# DSDPLC_IO.net
KiCad netlist of a schematic drawn in Altium Designer
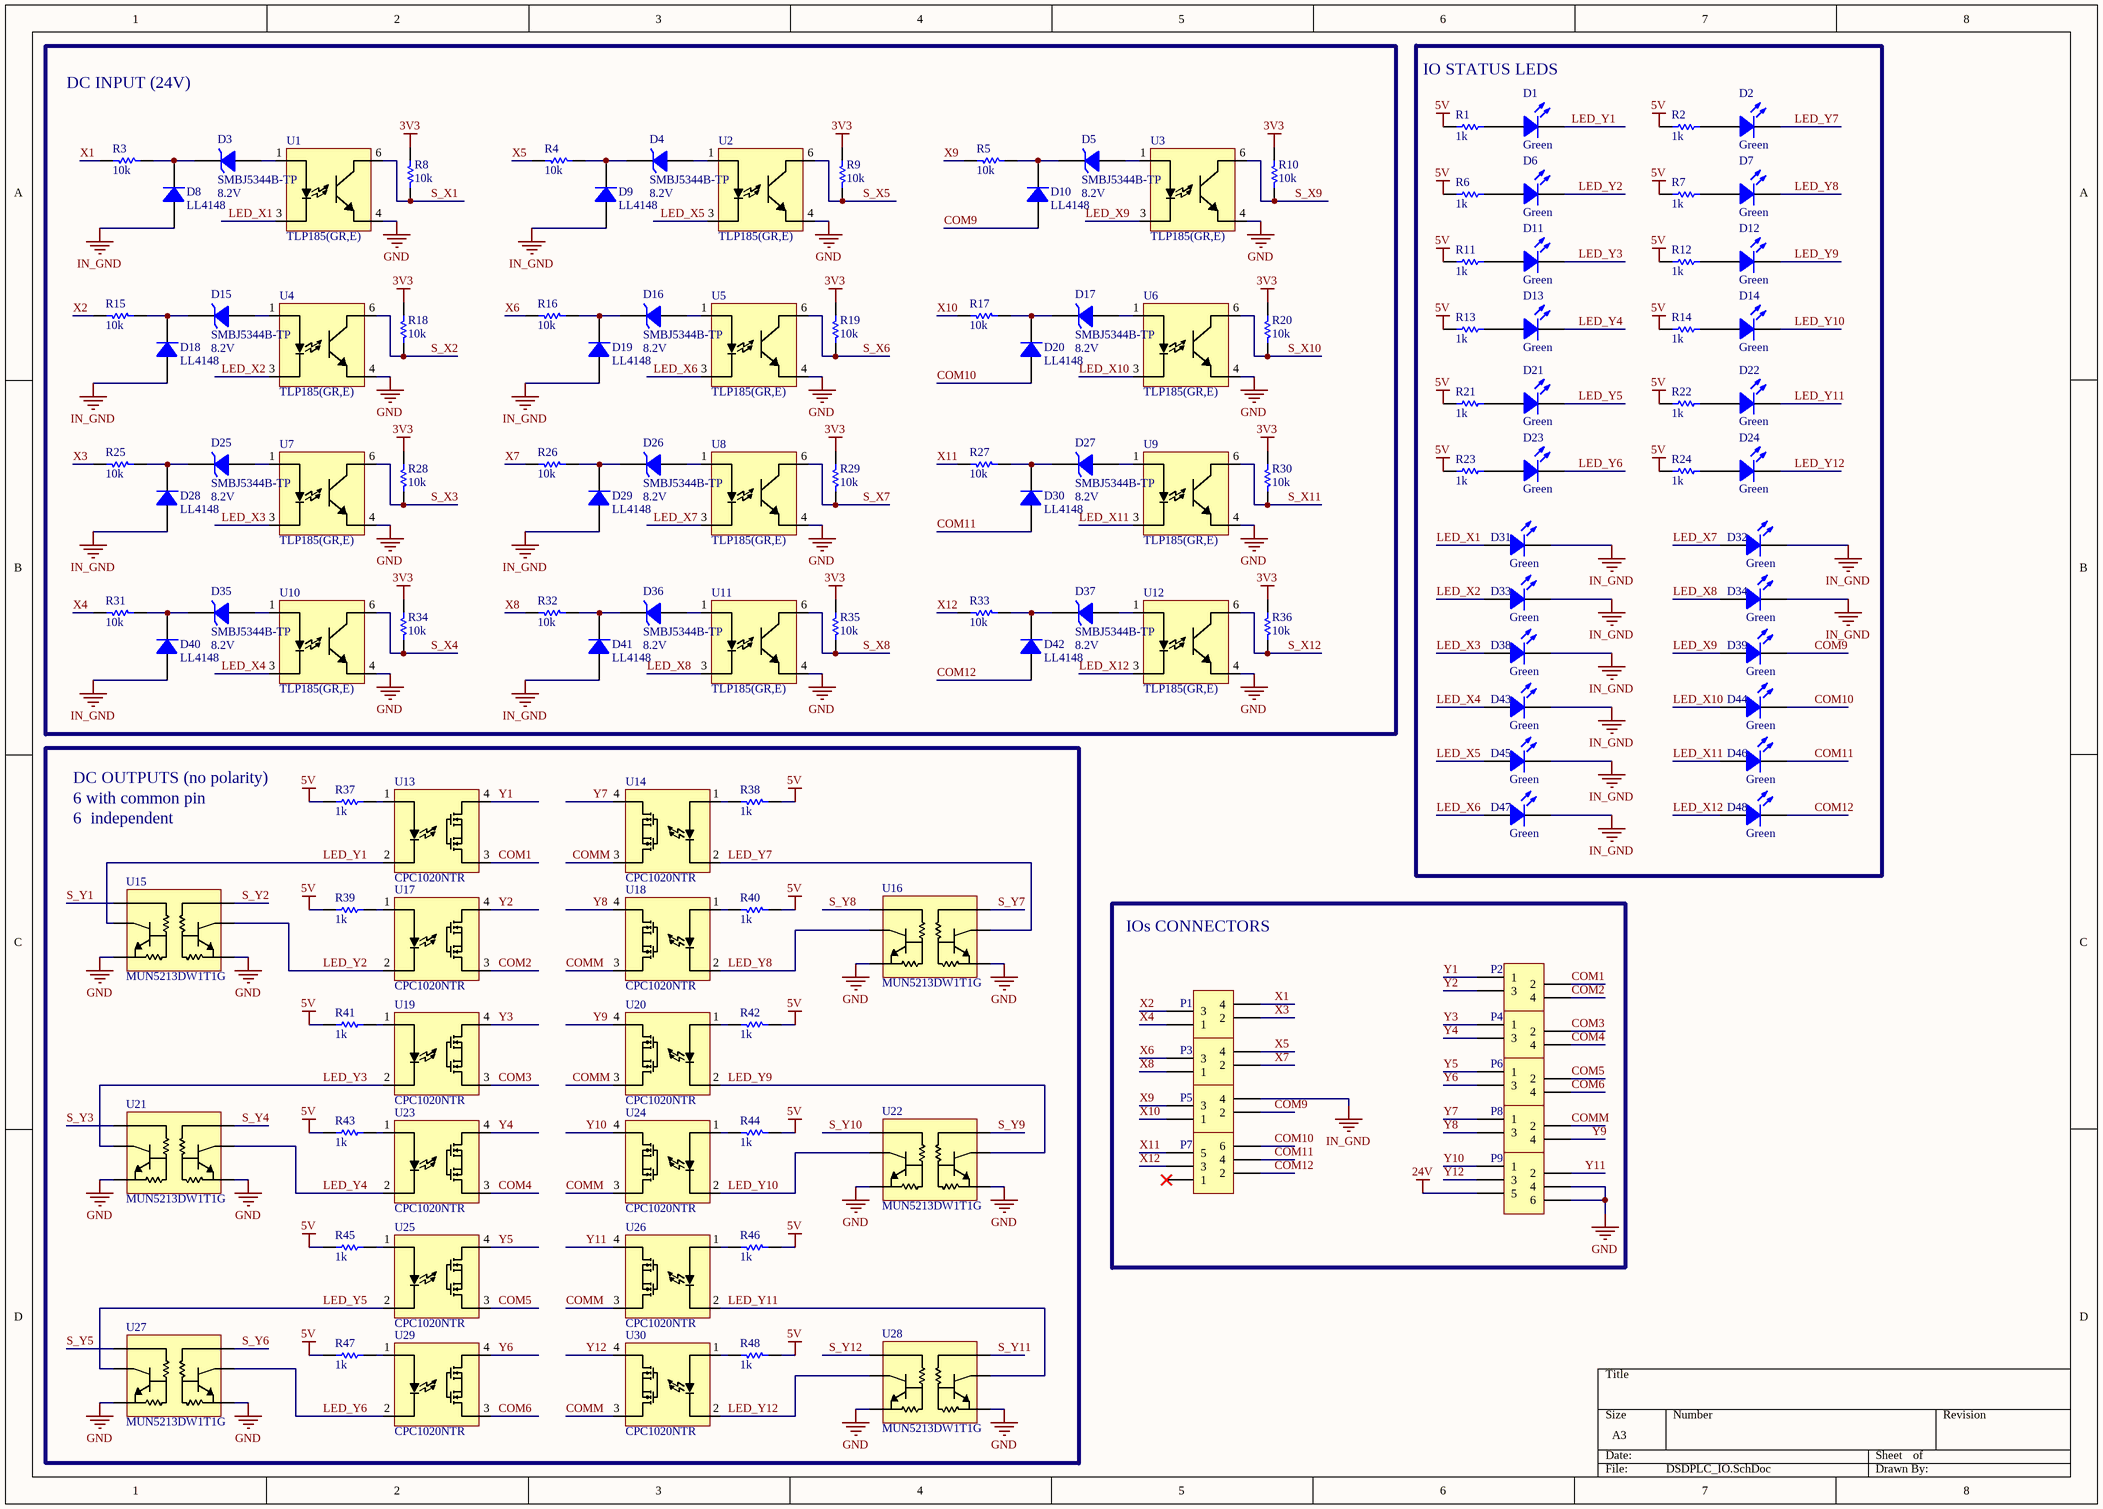
[diagram p0: DSDPLC_IO.SchDoc]

(export (version "E")
  (design (tool "Eeschema 10.0.6"))
  (components
    (comp (ref "D1")
      (value "Green")
      (footprint "R0603_N")
      (fields (field (name "COLOR") "Green"))
      (libsource (lib "General") (part "LED_SMD"))
    )
    (comp (ref "D2")
      (value "Green")
      (footprint "R0603_N")
      (fields (field (name "COLOR") "Green"))
      (libsource (lib "General") (part "LED_SMD"))
    )
    (comp (ref "D3")
      (value "SMBJ5344B-TP")
      (footprint "SMB_N")
      (description "DIODE ZENER 8.2V 5W DO214AA")
      (fields
        (field (name "MANUFACTURER") "Micro Commercial Co")
        (field (name "VOLTAGE - ZENER (NOM) (VZ)") "8.2V")
        (field (name "TOLERANCE") "±5%")
      )
      (libsource (lib "General") (part "SMBJ5344B-TP"))
    )
    (comp (ref "D4")
      (value "SMBJ5344B-TP")
      (footprint "SMB_N")
      (description "DIODE ZENER 8.2V 5W DO214AA")
      (fields
        (field (name "MANUFACTURER") "Micro Commercial Co")
        (field (name "VOLTAGE - ZENER (NOM) (VZ)") "8.2V")
        (field (name "TOLERANCE") "±5%")
      )
      (libsource (lib "General") (part "SMBJ5344B-TP"))
    )
    (comp (ref "D5")
      (value "SMBJ5344B-TP")
      (footprint "SMB_N")
      (description "DIODE ZENER 8.2V 5W DO214AA")
      (fields
        (field (name "MANUFACTURER") "Micro Commercial Co")
        (field (name "VOLTAGE - ZENER (NOM) (VZ)") "8.2V")
        (field (name "TOLERANCE") "±5%")
      )
      (libsource (lib "General") (part "SMBJ5344B-TP"))
    )
    (comp (ref "D6")
      (value "Green")
      (footprint "R0603_N")
      (fields (field (name "COLOR") "Green"))
      (libsource (lib "General") (part "LED_SMD"))
    )
    (comp (ref "D7")
      (value "Green")
      (footprint "R0603_N")
      (fields (field (name "COLOR") "Green"))
      (libsource (lib "General") (part "LED_SMD"))
    )
    (comp (ref "D8")
      (value "LL4148")
      (footprint "SOD-80_N")
      (description "DIODE SMALL SIG 100V 0.2A SOD80")
      (fields (field (name "MANUFACTURER") "Fairchild Semiconductor"))
      (libsource (lib "General") (part "LL4148"))
    )
    (comp (ref "D9")
      (value "LL4148")
      (footprint "SOD-80_N")
      (description "DIODE SMALL SIG 100V 0.2A SOD80")
      (fields (field (name "MANUFACTURER") "Fairchild Semiconductor"))
      (libsource (lib "General") (part "LL4148"))
    )
    (comp (ref "D10")
      (value "LL4148")
      (footprint "SOD-80_N")
      (description "DIODE SMALL SIG 100V 0.2A SOD80")
      (fields (field (name "MANUFACTURER") "Fairchild Semiconductor"))
      (libsource (lib "General") (part "LL4148"))
    )
    (comp (ref "D11")
      (value "Green")
      (footprint "R0603_N")
      (fields (field (name "COLOR") "Green"))
      (libsource (lib "General") (part "LED_SMD"))
    )
    (comp (ref "D12")
      (value "Green")
      (footprint "R0603_N")
      (fields (field (name "COLOR") "Green"))
      (libsource (lib "General") (part "LED_SMD"))
    )
    (comp (ref "D13")
      (value "Green")
      (footprint "R0603_N")
      (fields (field (name "COLOR") "Green"))
      (libsource (lib "General") (part "LED_SMD"))
    )
    (comp (ref "D14")
      (value "Green")
      (footprint "R0603_N")
      (fields (field (name "COLOR") "Green"))
      (libsource (lib "General") (part "LED_SMD"))
    )
    (comp (ref "D15")
      (value "SMBJ5344B-TP")
      (footprint "SMB_N")
      (description "DIODE ZENER 8.2V 5W DO214AA")
      (fields
        (field (name "MANUFACTURER") "Micro Commercial Co")
        (field (name "VOLTAGE - ZENER (NOM) (VZ)") "8.2V")
        (field (name "TOLERANCE") "±5%")
      )
      (libsource (lib "General") (part "SMBJ5344B-TP"))
    )
    (comp (ref "D16")
      (value "SMBJ5344B-TP")
      (footprint "SMB_N")
      (description "DIODE ZENER 8.2V 5W DO214AA")
      (fields
        (field (name "MANUFACTURER") "Micro Commercial Co")
        (field (name "VOLTAGE - ZENER (NOM) (VZ)") "8.2V")
        (field (name "TOLERANCE") "±5%")
      )
      (libsource (lib "General") (part "SMBJ5344B-TP"))
    )
    (comp (ref "D17")
      (value "SMBJ5344B-TP")
      (footprint "SMB_N")
      (description "DIODE ZENER 8.2V 5W DO214AA")
      (fields
        (field (name "MANUFACTURER") "Micro Commercial Co")
        (field (name "VOLTAGE - ZENER (NOM) (VZ)") "8.2V")
        (field (name "TOLERANCE") "±5%")
      )
      (libsource (lib "General") (part "SMBJ5344B-TP"))
    )
    (comp (ref "D18")
      (value "LL4148")
      (footprint "SOD-80_N")
      (description "DIODE SMALL SIG 100V 0.2A SOD80")
      (fields (field (name "MANUFACTURER") "Fairchild Semiconductor"))
      (libsource (lib "General") (part "LL4148"))
    )
    (comp (ref "D19")
      (value "LL4148")
      (footprint "SOD-80_N")
      (description "DIODE SMALL SIG 100V 0.2A SOD80")
      (fields (field (name "MANUFACTURER") "Fairchild Semiconductor"))
      (libsource (lib "General") (part "LL4148"))
    )
    (comp (ref "D20")
      (value "LL4148")
      (footprint "SOD-80_N")
      (description "DIODE SMALL SIG 100V 0.2A SOD80")
      (fields (field (name "MANUFACTURER") "Fairchild Semiconductor"))
      (libsource (lib "General") (part "LL4148"))
    )
    (comp (ref "D21")
      (value "Green")
      (footprint "R0603_N")
      (fields (field (name "COLOR") "Green"))
      (libsource (lib "General") (part "LED_SMD"))
    )
    (comp (ref "D22")
      (value "Green")
      (footprint "R0603_N")
      (fields (field (name "COLOR") "Green"))
      (libsource (lib "General") (part "LED_SMD"))
    )
    (comp (ref "D23")
      (value "Green")
      (footprint "R0603_N")
      (fields (field (name "COLOR") "Green"))
      (libsource (lib "General") (part "LED_SMD"))
    )
    (comp (ref "D24")
      (value "Green")
      (footprint "R0603_N")
      (fields (field (name "COLOR") "Green"))
      (libsource (lib "General") (part "LED_SMD"))
    )
    (comp (ref "D25")
      (value "SMBJ5344B-TP")
      (footprint "SMB_N")
      (description "DIODE ZENER 8.2V 5W DO214AA")
      (fields
        (field (name "MANUFACTURER") "Micro Commercial Co")
        (field (name "VOLTAGE - ZENER (NOM) (VZ)") "8.2V")
        (field (name "TOLERANCE") "±5%")
      )
      (libsource (lib "General") (part "SMBJ5344B-TP"))
    )
    (comp (ref "D26")
      (value "SMBJ5344B-TP")
      (footprint "SMB_N")
      (description "DIODE ZENER 8.2V 5W DO214AA")
      (fields
        (field (name "MANUFACTURER") "Micro Commercial Co")
        (field (name "VOLTAGE - ZENER (NOM) (VZ)") "8.2V")
        (field (name "TOLERANCE") "±5%")
      )
      (libsource (lib "General") (part "SMBJ5344B-TP"))
    )
    (comp (ref "D27")
      (value "SMBJ5344B-TP")
      (footprint "SMB_N")
      (description "DIODE ZENER 8.2V 5W DO214AA")
      (fields
        (field (name "MANUFACTURER") "Micro Commercial Co")
        (field (name "VOLTAGE - ZENER (NOM) (VZ)") "8.2V")
        (field (name "TOLERANCE") "±5%")
      )
      (libsource (lib "General") (part "SMBJ5344B-TP"))
    )
    (comp (ref "D28")
      (value "LL4148")
      (footprint "SOD-80_N")
      (description "DIODE SMALL SIG 100V 0.2A SOD80")
      (fields (field (name "MANUFACTURER") "Fairchild Semiconductor"))
      (libsource (lib "General") (part "LL4148"))
    )
    (comp (ref "D29")
      (value "LL4148")
      (footprint "SOD-80_N")
      (description "DIODE SMALL SIG 100V 0.2A SOD80")
      (fields (field (name "MANUFACTURER") "Fairchild Semiconductor"))
      (libsource (lib "General") (part "LL4148"))
    )
    (comp (ref "D30")
      (value "LL4148")
      (footprint "SOD-80_N")
      (description "DIODE SMALL SIG 100V 0.2A SOD80")
      (fields (field (name "MANUFACTURER") "Fairchild Semiconductor"))
      (libsource (lib "General") (part "LL4148"))
    )
    (comp (ref "D31")
      (value "Green")
      (footprint "R0603_N")
      (fields (field (name "COLOR") "Green"))
      (libsource (lib "General") (part "LED_SMD"))
    )
    (comp (ref "D32")
      (value "Green")
      (footprint "R0603_N")
      (fields (field (name "COLOR") "Green"))
      (libsource (lib "General") (part "LED_SMD"))
    )
    (comp (ref "D33")
      (value "Green")
      (footprint "R0603_N")
      (fields (field (name "COLOR") "Green"))
      (libsource (lib "General") (part "LED_SMD"))
    )
    (comp (ref "D34")
      (value "Green")
      (footprint "R0603_N")
      (fields (field (name "COLOR") "Green"))
      (libsource (lib "General") (part "LED_SMD"))
    )
    (comp (ref "D35")
      (value "SMBJ5344B-TP")
      (footprint "SMB_N")
      (description "DIODE ZENER 8.2V 5W DO214AA")
      (fields
        (field (name "MANUFACTURER") "Micro Commercial Co")
        (field (name "VOLTAGE - ZENER (NOM) (VZ)") "8.2V")
        (field (name "TOLERANCE") "±5%")
      )
      (libsource (lib "General") (part "SMBJ5344B-TP"))
    )
    (comp (ref "D36")
      (value "SMBJ5344B-TP")
      (footprint "SMB_N")
      (description "DIODE ZENER 8.2V 5W DO214AA")
      (fields
        (field (name "MANUFACTURER") "Micro Commercial Co")
        (field (name "VOLTAGE - ZENER (NOM) (VZ)") "8.2V")
        (field (name "TOLERANCE") "±5%")
      )
      (libsource (lib "General") (part "SMBJ5344B-TP"))
    )
    (comp (ref "D37")
      (value "SMBJ5344B-TP")
      (footprint "SMB_N")
      (description "DIODE ZENER 8.2V 5W DO214AA")
      (fields
        (field (name "MANUFACTURER") "Micro Commercial Co")
        (field (name "VOLTAGE - ZENER (NOM) (VZ)") "8.2V")
        (field (name "TOLERANCE") "±5%")
      )
      (libsource (lib "General") (part "SMBJ5344B-TP"))
    )
    (comp (ref "D38")
      (value "Green")
      (footprint "R0603_N")
      (fields (field (name "COLOR") "Green"))
      (libsource (lib "General") (part "LED_SMD"))
    )
    (comp (ref "D39")
      (value "Green")
      (footprint "R0603_N")
      (fields (field (name "COLOR") "Green"))
      (libsource (lib "General") (part "LED_SMD"))
    )
    (comp (ref "D40")
      (value "LL4148")
      (footprint "SOD-80_N")
      (description "DIODE SMALL SIG 100V 0.2A SOD80")
      (fields (field (name "MANUFACTURER") "Fairchild Semiconductor"))
      (libsource (lib "General") (part "LL4148"))
    )
    (comp (ref "D41")
      (value "LL4148")
      (footprint "SOD-80_N")
      (description "DIODE SMALL SIG 100V 0.2A SOD80")
      (fields (field (name "MANUFACTURER") "Fairchild Semiconductor"))
      (libsource (lib "General") (part "LL4148"))
    )
    (comp (ref "D42")
      (value "LL4148")
      (footprint "SOD-80_N")
      (description "DIODE SMALL SIG 100V 0.2A SOD80")
      (fields (field (name "MANUFACTURER") "Fairchild Semiconductor"))
      (libsource (lib "General") (part "LL4148"))
    )
    (comp (ref "D43")
      (value "Green")
      (footprint "R0603_N")
      (fields (field (name "COLOR") "Green"))
      (libsource (lib "General") (part "LED_SMD"))
    )
    (comp (ref "D44")
      (value "Green")
      (footprint "R0603_N")
      (fields (field (name "COLOR") "Green"))
      (libsource (lib "General") (part "LED_SMD"))
    )
    (comp (ref "D45")
      (value "Green")
      (footprint "R0603_N")
      (fields (field (name "COLOR") "Green"))
      (libsource (lib "General") (part "LED_SMD"))
    )
    (comp (ref "D46")
      (value "Green")
      (footprint "R0603_N")
      (fields (field (name "COLOR") "Green"))
      (libsource (lib "General") (part "LED_SMD"))
    )
    (comp (ref "D47")
      (value "Green")
      (footprint "R0603_N")
      (fields (field (name "COLOR") "Green"))
      (libsource (lib "General") (part "LED_SMD"))
    )
    (comp (ref "D48")
      (value "Green")
      (footprint "R0603_N")
      (fields (field (name "COLOR") "Green"))
      (libsource (lib "General") (part "LED_SMD"))
    )
    (comp (ref "P1")
      (value "BLOCK_CONN2X2")
      (footprint "block_conn 2 x 2")
      (description "TERM BLOCK 2POS STACK 5.08MM PC")
      (fields
        (field (name "MANUFACTURER") "TE Connectivity")
        (field (name "MANUFACTURER PART NUMBER") "796692-2")
      )
      (libsource (lib "") (part "BLOCK_CONN2X2_1"))
    )
    (comp (ref "P2")
      (value "BLOCK_CONN2X2")
      (footprint "block_conn 2 x 2")
      (description "TERM BLOCK 2POS STACK 5.08MM PC")
      (fields
        (field (name "MANUFACTURER") "TE Connectivity")
        (field (name "MANUFACTURER PART NUMBER") "796692-2")
      )
      (libsource (lib "General") (part "BLOCK_CONN2X2"))
    )
    (comp (ref "P3")
      (value "BLOCK_CONN2X2")
      (footprint "block_conn 2 x 2")
      (description "TERM BLOCK 2POS STACK 5.08MM PC")
      (fields
        (field (name "MANUFACTURER") "TE Connectivity")
        (field (name "MANUFACTURER PART NUMBER") "796692-2")
      )
      (libsource (lib "") (part "BLOCK_CONN2X2_1"))
    )
    (comp (ref "P4")
      (value "BLOCK_CONN2X2")
      (footprint "block_conn 2 x 2")
      (description "TERM BLOCK 2POS STACK 5.08MM PC")
      (fields
        (field (name "MANUFACTURER") "TE Connectivity")
        (field (name "MANUFACTURER PART NUMBER") "796692-2")
      )
      (libsource (lib "General") (part "BLOCK_CONN2X2"))
    )
    (comp (ref "P5")
      (value "BLOCK_CONN2X2")
      (footprint "block_conn 2 x 2")
      (description "TERM BLOCK 2POS STACK 5.08MM PC")
      (fields
        (field (name "MANUFACTURER") "TE Connectivity")
        (field (name "MANUFACTURER PART NUMBER") "796692-2")
      )
      (libsource (lib "") (part "BLOCK_CONN2X2_1"))
    )
    (comp (ref "P6")
      (value "BLOCK_CONN2X2")
      (footprint "block_conn 2 x 2")
      (description "TERM BLOCK 2POS STACK 5.08MM PC")
      (fields
        (field (name "MANUFACTURER") "TE Connectivity")
        (field (name "MANUFACTURER PART NUMBER") "796692-2")
      )
      (libsource (lib "General") (part "BLOCK_CONN2X2"))
    )
    (comp (ref "P7")
      (value "BLOCK_CONN2X3")
      (footprint "block_conn 2 x 3")
      (description "TERM BLOCK 3POS STACK 5.08MM PC")
      (fields
        (field (name "MANUFACTURER") "TE Connectivity")
        (field (name "MANUFACTURER PART NUMBER") "796692-3")
      )
      (libsource (lib "") (part "BLOCK_CONN2X3_1"))
    )
    (comp (ref "P8")
      (value "BLOCK_CONN2X2")
      (footprint "block_conn 2 x 2")
      (description "TERM BLOCK 2POS STACK 5.08MM PC")
      (fields
        (field (name "MANUFACTURER") "TE Connectivity")
        (field (name "MANUFACTURER PART NUMBER") "796692-2")
      )
      (libsource (lib "General") (part "BLOCK_CONN2X2"))
    )
    (comp (ref "P9")
      (value "BLOCK_CONN2X3")
      (footprint "block_conn 2 x 3")
      (description "TERM BLOCK 3POS STACK 5.08MM PC")
      (fields
        (field (name "MANUFACTURER") "TE Connectivity")
        (field (name "MANUFACTURER PART NUMBER") "796692-3")
      )
      (libsource (lib "General") (part "BLOCK_CONN2X3"))
    )
    (comp (ref "R1")
      (value "1k")
      (footprint "R0603_N")
      (fields (field (name "Comment") "R_SMD"))
      (libsource (lib "General") (part "R_SMD"))
    )
    (comp (ref "R2")
      (value "1k")
      (footprint "R0603_N")
      (fields (field (name "Comment") "R_SMD"))
      (libsource (lib "General") (part "R_SMD"))
    )
    (comp (ref "R3")
      (value "10k")
      (footprint "R0603_N")
      (fields (field (name "Comment") "R_SMD"))
      (libsource (lib "General") (part "R_SMD"))
    )
    (comp (ref "R4")
      (value "10k")
      (footprint "R0603_N")
      (fields (field (name "Comment") "R_SMD"))
      (libsource (lib "General") (part "R_SMD"))
    )
    (comp (ref "R5")
      (value "10k")
      (footprint "R0603_N")
      (fields (field (name "Comment") "R_SMD"))
      (libsource (lib "General") (part "R_SMD"))
    )
    (comp (ref "R6")
      (value "1k")
      (footprint "R0603_N")
      (fields (field (name "Comment") "R_SMD"))
      (libsource (lib "General") (part "R_SMD"))
    )
    (comp (ref "R7")
      (value "1k")
      (footprint "R0603_N")
      (fields (field (name "Comment") "R_SMD"))
      (libsource (lib "General") (part "R_SMD"))
    )
    (comp (ref "R8")
      (value "10k")
      (footprint "R0603_N")
      (fields (field (name "Comment") "R_SMD"))
      (libsource (lib "General") (part "R_SMD"))
    )
    (comp (ref "R9")
      (value "10k")
      (footprint "R0603_N")
      (fields (field (name "Comment") "R_SMD"))
      (libsource (lib "General") (part "R_SMD"))
    )
    (comp (ref "R10")
      (value "10k")
      (footprint "R0603_N")
      (fields (field (name "Comment") "R_SMD"))
      (libsource (lib "General") (part "R_SMD"))
    )
    (comp (ref "R11")
      (value "1k")
      (footprint "R0603_N")
      (fields (field (name "Comment") "R_SMD"))
      (libsource (lib "General") (part "R_SMD"))
    )
    (comp (ref "R12")
      (value "1k")
      (footprint "R0603_N")
      (fields (field (name "Comment") "R_SMD"))
      (libsource (lib "General") (part "R_SMD"))
    )
    (comp (ref "R13")
      (value "1k")
      (footprint "R0603_N")
      (fields (field (name "Comment") "R_SMD"))
      (libsource (lib "General") (part "R_SMD"))
    )
    (comp (ref "R14")
      (value "1k")
      (footprint "R0603_N")
      (fields (field (name "Comment") "R_SMD"))
      (libsource (lib "General") (part "R_SMD"))
    )
    (comp (ref "R15")
      (value "10k")
      (footprint "R0603_N")
      (fields (field (name "Comment") "R_SMD"))
      (libsource (lib "General") (part "R_SMD"))
    )
    (comp (ref "R16")
      (value "10k")
      (footprint "R0603_N")
      (fields (field (name "Comment") "R_SMD"))
      (libsource (lib "General") (part "R_SMD"))
    )
    (comp (ref "R17")
      (value "10k")
      (footprint "R0603_N")
      (fields (field (name "Comment") "R_SMD"))
      (libsource (lib "General") (part "R_SMD"))
    )
    (comp (ref "R18")
      (value "10k")
      (footprint "R0603_N")
      (fields (field (name "Comment") "R_SMD"))
      (libsource (lib "General") (part "R_SMD"))
    )
    (comp (ref "R19")
      (value "10k")
      (footprint "R0603_N")
      (fields (field (name "Comment") "R_SMD"))
      (libsource (lib "General") (part "R_SMD"))
    )
    (comp (ref "R20")
      (value "10k")
      (footprint "R0603_N")
      (fields (field (name "Comment") "R_SMD"))
      (libsource (lib "General") (part "R_SMD"))
    )
    (comp (ref "R21")
      (value "1k")
      (footprint "R0603_N")
      (fields (field (name "Comment") "R_SMD"))
      (libsource (lib "General") (part "R_SMD"))
    )
    (comp (ref "R22")
      (value "1k")
      (footprint "R0603_N")
      (fields (field (name "Comment") "R_SMD"))
      (libsource (lib "General") (part "R_SMD"))
    )
    (comp (ref "R23")
      (value "1k")
      (footprint "R0603_N")
      (fields (field (name "Comment") "R_SMD"))
      (libsource (lib "General") (part "R_SMD"))
    )
    (comp (ref "R24")
      (value "1k")
      (footprint "R0603_N")
      (fields (field (name "Comment") "R_SMD"))
      (libsource (lib "General") (part "R_SMD"))
    )
    (comp (ref "R25")
      (value "10k")
      (footprint "R0603_N")
      (fields (field (name "Comment") "R_SMD"))
      (libsource (lib "General") (part "R_SMD"))
    )
    (comp (ref "R26")
      (value "10k")
      (footprint "R0603_N")
      (fields (field (name "Comment") "R_SMD"))
      (libsource (lib "General") (part "R_SMD"))
    )
    (comp (ref "R27")
      (value "10k")
      (footprint "R0603_N")
      (fields (field (name "Comment") "R_SMD"))
      (libsource (lib "General") (part "R_SMD"))
    )
    (comp (ref "R28")
      (value "10k")
      (footprint "R0603_N")
      (fields (field (name "Comment") "R_SMD"))
      (libsource (lib "General") (part "R_SMD"))
    )
    (comp (ref "R29")
      (value "10k")
      (footprint "R0603_N")
      (fields (field (name "Comment") "R_SMD"))
      (libsource (lib "General") (part "R_SMD"))
    )
    (comp (ref "R30")
      (value "10k")
      (footprint "R0603_N")
      (fields (field (name "Comment") "R_SMD"))
      (libsource (lib "General") (part "R_SMD"))
    )
    (comp (ref "R31")
      (value "10k")
      (footprint "R0603_N")
      (fields (field (name "Comment") "R_SMD"))
      (libsource (lib "General") (part "R_SMD"))
    )
    (comp (ref "R32")
      (value "10k")
      (footprint "R0603_N")
      (fields (field (name "Comment") "R_SMD"))
      (libsource (lib "General") (part "R_SMD"))
    )
    (comp (ref "R33")
      (value "10k")
      (footprint "R0603_N")
      (fields (field (name "Comment") "R_SMD"))
      (libsource (lib "General") (part "R_SMD"))
    )
    (comp (ref "R34")
      (value "10k")
      (footprint "R0603_N")
      (fields (field (name "Comment") "R_SMD"))
      (libsource (lib "General") (part "R_SMD"))
    )
    (comp (ref "R35")
      (value "10k")
      (footprint "R0603_N")
      (fields (field (name "Comment") "R_SMD"))
      (libsource (lib "General") (part "R_SMD"))
    )
    (comp (ref "R36")
      (value "10k")
      (footprint "R0603_N")
      (fields (field (name "Comment") "R_SMD"))
      (libsource (lib "General") (part "R_SMD"))
    )
    (comp (ref "R37")
      (value "1k")
      (footprint "R0603_N")
      (fields (field (name "Comment") "R_SMD"))
      (libsource (lib "General") (part "R_SMD"))
    )
    (comp (ref "R38")
      (value "1k")
      (footprint "R0603_N")
      (fields (field (name "Comment") "R_SMD"))
      (libsource (lib "General") (part "R_SMD"))
    )
    (comp (ref "R39")
      (value "1k")
      (footprint "R0603_N")
      (fields (field (name "Comment") "R_SMD"))
      (libsource (lib "General") (part "R_SMD"))
    )
    (comp (ref "R40")
      (value "1k")
      (footprint "R0603_N")
      (fields (field (name "Comment") "R_SMD"))
      (libsource (lib "General") (part "R_SMD"))
    )
    (comp (ref "R41")
      (value "1k")
      (footprint "R0603_N")
      (fields (field (name "Comment") "R_SMD"))
      (libsource (lib "General") (part "R_SMD"))
    )
    (comp (ref "R42")
      (value "1k")
      (footprint "R0603_N")
      (fields (field (name "Comment") "R_SMD"))
      (libsource (lib "General") (part "R_SMD"))
    )
    (comp (ref "R43")
      (value "1k")
      (footprint "R0603_N")
      (fields (field (name "Comment") "R_SMD"))
      (libsource (lib "General") (part "R_SMD"))
    )
    (comp (ref "R44")
      (value "1k")
      (footprint "R0603_N")
      (fields (field (name "Comment") "R_SMD"))
      (libsource (lib "General") (part "R_SMD"))
    )
    (comp (ref "R45")
      (value "1k")
      (footprint "R0603_N")
      (fields (field (name "Comment") "R_SMD"))
      (libsource (lib "General") (part "R_SMD"))
    )
    (comp (ref "R46")
      (value "1k")
      (footprint "R0603_N")
      (fields (field (name "Comment") "R_SMD"))
      (libsource (lib "General") (part "R_SMD"))
    )
    (comp (ref "R47")
      (value "1k")
      (footprint "R0603_N")
      (fields (field (name "Comment") "R_SMD"))
      (libsource (lib "General") (part "R_SMD"))
    )
    (comp (ref "R48")
      (value "1k")
      (footprint "R0603_N")
      (fields (field (name "Comment") "R_SMD"))
      (libsource (lib "General") (part "R_SMD"))
    )
    (comp (ref "U1")
      (value "TLP185(GR,E)")
      (footprint "SOIC6 (4 leads)")
      (description "OPTOISO 3.75KV TRANS 6-SO 4 LEAD")
      (fields (field (name "MANUFACTURER") "Toshiba Semiconductor and Storage"))
      (libsource (lib "General") (part "TLP185(GR,E)"))
    )
    (comp (ref "U2")
      (value "TLP185(GR,E)")
      (footprint "SOIC6 (4 leads)")
      (description "OPTOISO 3.75KV TRANS 6-SO 4 LEAD")
      (fields (field (name "MANUFACTURER") "Toshiba Semiconductor and Storage"))
      (libsource (lib "General") (part "TLP185(GR,E)"))
    )
    (comp (ref "U3")
      (value "TLP185(GR,E)")
      (footprint "SOIC6 (4 leads)")
      (description "OPTOISO 3.75KV TRANS 6-SO 4 LEAD")
      (fields (field (name "MANUFACTURER") "Toshiba Semiconductor and Storage"))
      (libsource (lib "General") (part "TLP185(GR,E)"))
    )
    (comp (ref "U4")
      (value "TLP185(GR,E)")
      (footprint "SOIC6 (4 leads)")
      (description "OPTOISO 3.75KV TRANS 6-SO 4 LEAD")
      (fields (field (name "MANUFACTURER") "Toshiba Semiconductor and Storage"))
      (libsource (lib "General") (part "TLP185(GR,E)"))
    )
    (comp (ref "U5")
      (value "TLP185(GR,E)")
      (footprint "SOIC6 (4 leads)")
      (description "OPTOISO 3.75KV TRANS 6-SO 4 LEAD")
      (fields (field (name "MANUFACTURER") "Toshiba Semiconductor and Storage"))
      (libsource (lib "General") (part "TLP185(GR,E)"))
    )
    (comp (ref "U6")
      (value "TLP185(GR,E)")
      (footprint "SOIC6 (4 leads)")
      (description "OPTOISO 3.75KV TRANS 6-SO 4 LEAD")
      (fields (field (name "MANUFACTURER") "Toshiba Semiconductor and Storage"))
      (libsource (lib "General") (part "TLP185(GR,E)"))
    )
    (comp (ref "U7")
      (value "TLP185(GR,E)")
      (footprint "SOIC6 (4 leads)")
      (description "OPTOISO 3.75KV TRANS 6-SO 4 LEAD")
      (fields (field (name "MANUFACTURER") "Toshiba Semiconductor and Storage"))
      (libsource (lib "General") (part "TLP185(GR,E)"))
    )
    (comp (ref "U8")
      (value "TLP185(GR,E)")
      (footprint "SOIC6 (4 leads)")
      (description "OPTOISO 3.75KV TRANS 6-SO 4 LEAD")
      (fields (field (name "MANUFACTURER") "Toshiba Semiconductor and Storage"))
      (libsource (lib "General") (part "TLP185(GR,E)"))
    )
    (comp (ref "U9")
      (value "TLP185(GR,E)")
      (footprint "SOIC6 (4 leads)")
      (description "OPTOISO 3.75KV TRANS 6-SO 4 LEAD")
      (fields (field (name "MANUFACTURER") "Toshiba Semiconductor and Storage"))
      (libsource (lib "General") (part "TLP185(GR,E)"))
    )
    (comp (ref "U10")
      (value "TLP185(GR,E)")
      (footprint "SOIC6 (4 leads)")
      (description "OPTOISO 3.75KV TRANS 6-SO 4 LEAD")
      (fields (field (name "MANUFACTURER") "Toshiba Semiconductor and Storage"))
      (libsource (lib "General") (part "TLP185(GR,E)"))
    )
    (comp (ref "U11")
      (value "TLP185(GR,E)")
      (footprint "SOIC6 (4 leads)")
      (description "OPTOISO 3.75KV TRANS 6-SO 4 LEAD")
      (fields (field (name "MANUFACTURER") "Toshiba Semiconductor and Storage"))
      (libsource (lib "General") (part "TLP185(GR,E)"))
    )
    (comp (ref "U12")
      (value "TLP185(GR,E)")
      (footprint "SOIC6 (4 leads)")
      (description "OPTOISO 3.75KV TRANS 6-SO 4 LEAD")
      (fields (field (name "MANUFACTURER") "Toshiba Semiconductor and Storage"))
      (libsource (lib "General") (part "TLP185(GR,E)"))
    )
    (comp (ref "U13")
      (value "CPC1020NTR")
      (footprint "SOP4_N")
      (description "RELAY OPTOMOS 1200MA 4-SOP")
      (fields (field (name "MANUFACTURER") "IXYS Integrated Circuits Division"))
      (libsource (lib "General") (part "CPC1020NTR"))
    )
    (comp (ref "U14")
      (value "CPC1020NTR")
      (footprint "SOP4_N")
      (description "RELAY OPTOMOS 1200MA 4-SOP")
      (fields (field (name "MANUFACTURER") "IXYS Integrated Circuits Division"))
      (libsource (lib "General") (part "CPC1020NTR"))
    )
    (comp (ref "U15")
      (value "MUN5213DW1T1G")
      (footprint "SOT363_N")
      (description "TRANS PREBIAS DUAL NPN SOT363")
      (fields (field (name "MANUFACTURER") "ON Semiconductor"))
      (libsource (lib "") (part "MUN5213DW1T1G_1"))
    )
    (comp (ref "U16")
      (value "MUN5213DW1T1G")
      (footprint "SOT363_N")
      (description "TRANS PREBIAS DUAL NPN SOT363")
      (fields (field (name "MANUFACTURER") "ON Semiconductor"))
      (libsource (lib "General") (part "MUN5213DW1T1G"))
    )
    (comp (ref "U17")
      (value "CPC1020NTR")
      (footprint "SOP4_N")
      (description "RELAY OPTOMOS 1200MA 4-SOP")
      (fields (field (name "MANUFACTURER") "IXYS Integrated Circuits Division"))
      (libsource (lib "General") (part "CPC1020NTR"))
    )
    (comp (ref "U18")
      (value "CPC1020NTR")
      (footprint "SOP4_N")
      (description "RELAY OPTOMOS 1200MA 4-SOP")
      (fields (field (name "MANUFACTURER") "IXYS Integrated Circuits Division"))
      (libsource (lib "General") (part "CPC1020NTR"))
    )
    (comp (ref "U19")
      (value "CPC1020NTR")
      (footprint "SOP4_N")
      (description "RELAY OPTOMOS 1200MA 4-SOP")
      (fields (field (name "MANUFACTURER") "IXYS Integrated Circuits Division"))
      (libsource (lib "General") (part "CPC1020NTR"))
    )
    (comp (ref "U20")
      (value "CPC1020NTR")
      (footprint "SOP4_N")
      (description "RELAY OPTOMOS 1200MA 4-SOP")
      (fields (field (name "MANUFACTURER") "IXYS Integrated Circuits Division"))
      (libsource (lib "General") (part "CPC1020NTR"))
    )
    (comp (ref "U21")
      (value "MUN5213DW1T1G")
      (footprint "SOT363_N")
      (description "TRANS PREBIAS DUAL NPN SOT363")
      (fields (field (name "MANUFACTURER") "ON Semiconductor"))
      (libsource (lib "") (part "MUN5213DW1T1G_1"))
    )
    (comp (ref "U22")
      (value "MUN5213DW1T1G")
      (footprint "SOT363_N")
      (description "TRANS PREBIAS DUAL NPN SOT363")
      (fields (field (name "MANUFACTURER") "ON Semiconductor"))
      (libsource (lib "General") (part "MUN5213DW1T1G"))
    )
    (comp (ref "U23")
      (value "CPC1020NTR")
      (footprint "SOP4_N")
      (description "RELAY OPTOMOS 1200MA 4-SOP")
      (fields (field (name "MANUFACTURER") "IXYS Integrated Circuits Division"))
      (libsource (lib "General") (part "CPC1020NTR"))
    )
    (comp (ref "U24")
      (value "CPC1020NTR")
      (footprint "SOP4_N")
      (description "RELAY OPTOMOS 1200MA 4-SOP")
      (fields (field (name "MANUFACTURER") "IXYS Integrated Circuits Division"))
      (libsource (lib "General") (part "CPC1020NTR"))
    )
    (comp (ref "U25")
      (value "CPC1020NTR")
      (footprint "SOP4_N")
      (description "RELAY OPTOMOS 1200MA 4-SOP")
      (fields (field (name "MANUFACTURER") "IXYS Integrated Circuits Division"))
      (libsource (lib "General") (part "CPC1020NTR"))
    )
    (comp (ref "U26")
      (value "CPC1020NTR")
      (footprint "SOP4_N")
      (description "RELAY OPTOMOS 1200MA 4-SOP")
      (fields (field (name "MANUFACTURER") "IXYS Integrated Circuits Division"))
      (libsource (lib "General") (part "CPC1020NTR"))
    )
    (comp (ref "U27")
      (value "MUN5213DW1T1G")
      (footprint "SOT363_N")
      (description "TRANS PREBIAS DUAL NPN SOT363")
      (fields (field (name "MANUFACTURER") "ON Semiconductor"))
      (libsource (lib "") (part "MUN5213DW1T1G_1"))
    )
    (comp (ref "U28")
      (value "MUN5213DW1T1G")
      (footprint "SOT363_N")
      (description "TRANS PREBIAS DUAL NPN SOT363")
      (fields (field (name "MANUFACTURER") "ON Semiconductor"))
      (libsource (lib "General") (part "MUN5213DW1T1G"))
    )
    (comp (ref "U29")
      (value "CPC1020NTR")
      (footprint "SOP4_N")
      (description "RELAY OPTOMOS 1200MA 4-SOP")
      (fields (field (name "MANUFACTURER") "IXYS Integrated Circuits Division"))
      (libsource (lib "General") (part "CPC1020NTR"))
    )
    (comp (ref "U30")
      (value "CPC1020NTR")
      (footprint "SOP4_N")
      (description "RELAY OPTOMOS 1200MA 4-SOP")
      (fields (field (name "MANUFACTURER") "IXYS Integrated Circuits Division"))
      (libsource (lib "General") (part "CPC1020NTR"))
    )
  )
  (nets
    (net (code "1") (name "/COM1") (class "Default")
      (node (ref "P2") (pin "2") (pinfunction "2_2") (pintype "passive"))
      (node (ref "U13") (pin "3") (pinfunction "DC-_3") (pintype "passive"))
    )
    (net (code "2") (name "/COM2") (class "Default")
      (node (ref "P2") (pin "4") (pinfunction "4_4") (pintype "passive"))
      (node (ref "U17") (pin "3") (pinfunction "DC-_3") (pintype "passive"))
    )
    (net (code "3") (name "/COM3") (class "Default")
      (node (ref "P4") (pin "2") (pinfunction "2_2") (pintype "passive"))
      (node (ref "U19") (pin "3") (pinfunction "DC-_3") (pintype "passive"))
    )
    (net (code "4") (name "/COM4") (class "Default")
      (node (ref "P4") (pin "4") (pinfunction "4_4") (pintype "passive"))
      (node (ref "U23") (pin "3") (pinfunction "DC-_3") (pintype "passive"))
    )
    (net (code "5") (name "/COM5") (class "Default")
      (node (ref "P6") (pin "2") (pinfunction "2_2") (pintype "passive"))
      (node (ref "U25") (pin "3") (pinfunction "DC-_3") (pintype "passive"))
    )
    (net (code "6") (name "/COM6") (class "Default")
      (node (ref "P6") (pin "4") (pinfunction "4_4") (pintype "passive"))
      (node (ref "U29") (pin "3") (pinfunction "DC-_3") (pintype "passive"))
    )
    (net (code "7") (name "/COM9") (class "Default")
      (node (ref "D10") (pin "1") (pinfunction "A_1") (pintype "passive"))
      (node (ref "D39") (pin "2") (pinfunction "K_2") (pintype "passive"))
      (node (ref "P5") (pin "2") (pinfunction "2_2") (pintype "passive"))
    )
    (net (code "8") (name "/COM10") (class "Default")
      (node (ref "D20") (pin "1") (pinfunction "A_1") (pintype "passive"))
      (node (ref "D44") (pin "2") (pinfunction "K_2") (pintype "passive"))
      (node (ref "P7") (pin "6") (pinfunction "6_6") (pintype "passive"))
    )
    (net (code "9") (name "/COM11") (class "Default")
      (node (ref "D30") (pin "1") (pinfunction "A_1") (pintype "passive"))
      (node (ref "D46") (pin "2") (pinfunction "K_2") (pintype "passive"))
      (node (ref "P7") (pin "4") (pinfunction "4_4") (pintype "passive"))
    )
    (net (code "10") (name "/COM12") (class "Default")
      (node (ref "D42") (pin "1") (pinfunction "A_1") (pintype "passive"))
      (node (ref "D48") (pin "2") (pinfunction "K_2") (pintype "passive"))
      (node (ref "P7") (pin "2") (pinfunction "2_2") (pintype "passive"))
    )
    (net (code "11") (name "/COMM") (class "Default")
      (node (ref "P8") (pin "2") (pinfunction "2_2") (pintype "passive"))
      (node (ref "U14") (pin "3") (pinfunction "DC-_3") (pintype "passive"))
      (node (ref "U18") (pin "3") (pinfunction "DC-_3") (pintype "passive"))
      (node (ref "U20") (pin "3") (pinfunction "DC-_3") (pintype "passive"))
      (node (ref "U24") (pin "3") (pinfunction "DC-_3") (pintype "passive"))
      (node (ref "U26") (pin "3") (pinfunction "DC-_3") (pintype "passive"))
      (node (ref "U30") (pin "3") (pinfunction "DC-_3") (pintype "passive"))
    )
    (net (code "12") (name "/LED_X1") (class "Default")
      (node (ref "D31") (pin "1") (pinfunction "A_1") (pintype "passive"))
      (node (ref "U1") (pin "3") (pinfunction "control-_3") (pintype "passive"))
    )
    (net (code "13") (name "/LED_X2") (class "Default")
      (node (ref "D33") (pin "1") (pinfunction "A_1") (pintype "passive"))
      (node (ref "U4") (pin "3") (pinfunction "control-_3") (pintype "passive"))
    )
    (net (code "14") (name "/LED_X3") (class "Default")
      (node (ref "D38") (pin "1") (pinfunction "A_1") (pintype "passive"))
      (node (ref "U7") (pin "3") (pinfunction "control-_3") (pintype "passive"))
    )
    (net (code "15") (name "/LED_X4") (class "Default")
      (node (ref "D43") (pin "1") (pinfunction "A_1") (pintype "passive"))
      (node (ref "U10") (pin "3") (pinfunction "control-_3") (pintype "passive"))
    )
    (net (code "16") (name "/LED_X5") (class "Default")
      (node (ref "D45") (pin "1") (pinfunction "A_1") (pintype "passive"))
      (node (ref "U2") (pin "3") (pinfunction "control-_3") (pintype "passive"))
    )
    (net (code "17") (name "/LED_X6") (class "Default")
      (node (ref "D47") (pin "1") (pinfunction "A_1") (pintype "passive"))
      (node (ref "U5") (pin "3") (pinfunction "control-_3") (pintype "passive"))
    )
    (net (code "18") (name "/LED_X7") (class "Default")
      (node (ref "D32") (pin "1") (pinfunction "A_1") (pintype "passive"))
      (node (ref "U8") (pin "3") (pinfunction "control-_3") (pintype "passive"))
    )
    (net (code "19") (name "/LED_X8") (class "Default")
      (node (ref "D34") (pin "1") (pinfunction "A_1") (pintype "passive"))
      (node (ref "U11") (pin "3") (pinfunction "control-_3") (pintype "passive"))
    )
    (net (code "20") (name "/LED_X9") (class "Default")
      (node (ref "D39") (pin "1") (pinfunction "A_1") (pintype "passive"))
      (node (ref "U3") (pin "3") (pinfunction "control-_3") (pintype "passive"))
    )
    (net (code "21") (name "/LED_X10") (class "Default")
      (node (ref "D44") (pin "1") (pinfunction "A_1") (pintype "passive"))
      (node (ref "U6") (pin "3") (pinfunction "control-_3") (pintype "passive"))
    )
    (net (code "22") (name "/LED_X11") (class "Default")
      (node (ref "D46") (pin "1") (pinfunction "A_1") (pintype "passive"))
      (node (ref "U9") (pin "3") (pinfunction "control-_3") (pintype "passive"))
    )
    (net (code "23") (name "/LED_X12") (class "Default")
      (node (ref "D48") (pin "1") (pinfunction "A_1") (pintype "passive"))
      (node (ref "U12") (pin "3") (pinfunction "control-_3") (pintype "passive"))
    )
    (net (code "24") (name "/LED_Y1") (class "Default")
      (node (ref "D1") (pin "2") (pinfunction "K_2") (pintype "passive"))
      (node (ref "U13") (pin "2") (pinfunction "control-_2") (pintype "passive"))
      (node (ref "U15") (pin "6") (pinfunction "b_6") (pintype "passive"))
    )
    (net (code "25") (name "/LED_Y2") (class "Default")
      (node (ref "D6") (pin "2") (pinfunction "K_2") (pintype "passive"))
      (node (ref "U15") (pin "3") (pinfunction "*_3") (pintype "passive"))
      (node (ref "U17") (pin "2") (pinfunction "control-_2") (pintype "passive"))
    )
    (net (code "26") (name "/LED_Y3") (class "Default")
      (node (ref "D11") (pin "2") (pinfunction "K_2") (pintype "passive"))
      (node (ref "U19") (pin "2") (pinfunction "control-_2") (pintype "passive"))
      (node (ref "U21") (pin "6") (pinfunction "b_6") (pintype "passive"))
    )
    (net (code "27") (name "/LED_Y4") (class "Default")
      (node (ref "D13") (pin "2") (pinfunction "K_2") (pintype "passive"))
      (node (ref "U21") (pin "3") (pinfunction "*_3") (pintype "passive"))
      (node (ref "U23") (pin "2") (pinfunction "control-_2") (pintype "passive"))
    )
    (net (code "28") (name "/LED_Y5") (class "Default")
      (node (ref "D21") (pin "2") (pinfunction "K_2") (pintype "passive"))
      (node (ref "U25") (pin "2") (pinfunction "control-_2") (pintype "passive"))
      (node (ref "U27") (pin "6") (pinfunction "b_6") (pintype "passive"))
    )
    (net (code "29") (name "/LED_Y6") (class "Default")
      (node (ref "D23") (pin "2") (pinfunction "K_2") (pintype "passive"))
      (node (ref "U27") (pin "3") (pinfunction "*_3") (pintype "passive"))
      (node (ref "U29") (pin "2") (pinfunction "control-_2") (pintype "passive"))
    )
    (net (code "30") (name "/LED_Y7") (class "Default")
      (node (ref "D2") (pin "2") (pinfunction "K_2") (pintype "passive"))
      (node (ref "U14") (pin "2") (pinfunction "control-_2") (pintype "passive"))
      (node (ref "U16") (pin "6") (pinfunction "b_6") (pintype "passive"))
    )
    (net (code "31") (name "/LED_Y8") (class "Default")
      (node (ref "D7") (pin "2") (pinfunction "K_2") (pintype "passive"))
      (node (ref "U16") (pin "3") (pinfunction "*_3") (pintype "passive"))
      (node (ref "U18") (pin "2") (pinfunction "control-_2") (pintype "passive"))
    )
    (net (code "32") (name "/LED_Y9") (class "Default")
      (node (ref "D12") (pin "2") (pinfunction "K_2") (pintype "passive"))
      (node (ref "U20") (pin "2") (pinfunction "control-_2") (pintype "passive"))
      (node (ref "U22") (pin "6") (pinfunction "b_6") (pintype "passive"))
    )
    (net (code "33") (name "/LED_Y10") (class "Default")
      (node (ref "D14") (pin "2") (pinfunction "K_2") (pintype "passive"))
      (node (ref "U22") (pin "3") (pinfunction "*_3") (pintype "passive"))
      (node (ref "U24") (pin "2") (pinfunction "control-_2") (pintype "passive"))
    )
    (net (code "34") (name "/LED_Y11") (class "Default")
      (node (ref "D22") (pin "2") (pinfunction "K_2") (pintype "passive"))
      (node (ref "U26") (pin "2") (pinfunction "control-_2") (pintype "passive"))
      (node (ref "U28") (pin "6") (pinfunction "b_6") (pintype "passive"))
    )
    (net (code "35") (name "/LED_Y12") (class "Default")
      (node (ref "D24") (pin "2") (pinfunction "K_2") (pintype "passive"))
      (node (ref "U28") (pin "3") (pinfunction "*_3") (pintype "passive"))
      (node (ref "U30") (pin "2") (pinfunction "control-_2") (pintype "passive"))
    )
    (net (code "36") (name "/S_X1") (class "Default")
      (node (ref "R8") (pin "1") (pinfunction "1_1") (pintype "passive"))
      (node (ref "U1") (pin "6") (pinfunction "DC+_6") (pintype "passive"))
    )
    (net (code "37") (name "/S_X2") (class "Default")
      (node (ref "R18") (pin "1") (pinfunction "1_1") (pintype "passive"))
      (node (ref "U4") (pin "6") (pinfunction "DC+_6") (pintype "passive"))
    )
    (net (code "38") (name "/S_X3") (class "Default")
      (node (ref "R28") (pin "1") (pinfunction "1_1") (pintype "passive"))
      (node (ref "U7") (pin "6") (pinfunction "DC+_6") (pintype "passive"))
    )
    (net (code "39") (name "/S_X4") (class "Default")
      (node (ref "R34") (pin "1") (pinfunction "1_1") (pintype "passive"))
      (node (ref "U10") (pin "6") (pinfunction "DC+_6") (pintype "passive"))
    )
    (net (code "40") (name "/S_X5") (class "Default")
      (node (ref "R9") (pin "1") (pinfunction "1_1") (pintype "passive"))
      (node (ref "U2") (pin "6") (pinfunction "DC+_6") (pintype "passive"))
    )
    (net (code "41") (name "/S_X6") (class "Default")
      (node (ref "R19") (pin "1") (pinfunction "1_1") (pintype "passive"))
      (node (ref "U5") (pin "6") (pinfunction "DC+_6") (pintype "passive"))
    )
    (net (code "42") (name "/S_X7") (class "Default")
      (node (ref "R29") (pin "1") (pinfunction "1_1") (pintype "passive"))
      (node (ref "U8") (pin "6") (pinfunction "DC+_6") (pintype "passive"))
    )
    (net (code "43") (name "/S_X8") (class "Default")
      (node (ref "R35") (pin "1") (pinfunction "1_1") (pintype "passive"))
      (node (ref "U11") (pin "6") (pinfunction "DC+_6") (pintype "passive"))
    )
    (net (code "44") (name "/S_X9") (class "Default")
      (node (ref "R10") (pin "1") (pinfunction "1_1") (pintype "passive"))
      (node (ref "U3") (pin "6") (pinfunction "DC+_6") (pintype "passive"))
    )
    (net (code "45") (name "/S_X10") (class "Default")
      (node (ref "R20") (pin "1") (pinfunction "1_1") (pintype "passive"))
      (node (ref "U6") (pin "6") (pinfunction "DC+_6") (pintype "passive"))
    )
    (net (code "46") (name "/S_X11") (class "Default")
      (node (ref "R30") (pin "1") (pinfunction "1_1") (pintype "passive"))
      (node (ref "U9") (pin "6") (pinfunction "DC+_6") (pintype "passive"))
    )
    (net (code "47") (name "/S_X12") (class "Default")
      (node (ref "R36") (pin "1") (pinfunction "1_1") (pintype "passive"))
      (node (ref "U12") (pin "6") (pinfunction "DC+_6") (pintype "passive"))
    )
    (net (code "48") (name "/S_Y1") (class "Default")
      (node (ref "U15") (pin "2") (pinfunction "*_2") (pintype "passive"))
    )
    (net (code "49") (name "/S_Y2") (class "Default")
      (node (ref "U15") (pin "5") (pinfunction "*_5") (pintype "passive"))
    )
    (net (code "50") (name "/S_Y3") (class "Default")
      (node (ref "U21") (pin "2") (pinfunction "*_2") (pintype "passive"))
    )
    (net (code "51") (name "/S_Y4") (class "Default")
      (node (ref "U21") (pin "5") (pinfunction "*_5") (pintype "passive"))
    )
    (net (code "52") (name "/S_Y5") (class "Default")
      (node (ref "U27") (pin "2") (pinfunction "*_2") (pintype "passive"))
    )
    (net (code "53") (name "/S_Y6") (class "Default")
      (node (ref "U27") (pin "5") (pinfunction "*_5") (pintype "passive"))
    )
    (net (code "54") (name "/S_Y7") (class "Default")
      (node (ref "U16") (pin "2") (pinfunction "*_2") (pintype "passive"))
    )
    (net (code "55") (name "/S_Y8") (class "Default")
      (node (ref "U16") (pin "5") (pinfunction "*_5") (pintype "passive"))
    )
    (net (code "56") (name "/S_Y9") (class "Default")
      (node (ref "U22") (pin "2") (pinfunction "*_2") (pintype "passive"))
    )
    (net (code "57") (name "/S_Y10") (class "Default")
      (node (ref "U22") (pin "5") (pinfunction "*_5") (pintype "passive"))
    )
    (net (code "58") (name "/S_Y11") (class "Default")
      (node (ref "U28") (pin "2") (pinfunction "*_2") (pintype "passive"))
    )
    (net (code "59") (name "/S_Y12") (class "Default")
      (node (ref "U28") (pin "5") (pinfunction "*_5") (pintype "passive"))
    )
    (net (code "60") (name "/X1") (class "Default")
      (node (ref "P1") (pin "4") (pinfunction "4_4") (pintype "passive"))
      (node (ref "R3") (pin "2") (pinfunction "2_2") (pintype "passive"))
    )
    (net (code "61") (name "/X2") (class "Default")
      (node (ref "P1") (pin "3") (pinfunction "3_3") (pintype "passive"))
      (node (ref "R15") (pin "2") (pinfunction "2_2") (pintype "passive"))
    )
    (net (code "62") (name "/X3") (class "Default")
      (node (ref "P1") (pin "2") (pinfunction "2_2") (pintype "passive"))
      (node (ref "R25") (pin "2") (pinfunction "2_2") (pintype "passive"))
    )
    (net (code "63") (name "/X4") (class "Default")
      (node (ref "P1") (pin "1") (pinfunction "1_1") (pintype "passive"))
      (node (ref "R31") (pin "2") (pinfunction "2_2") (pintype "passive"))
    )
    (net (code "64") (name "/X5") (class "Default")
      (node (ref "P3") (pin "4") (pinfunction "4_4") (pintype "passive"))
      (node (ref "R4") (pin "2") (pinfunction "2_2") (pintype "passive"))
    )
    (net (code "65") (name "/X6") (class "Default")
      (node (ref "P3") (pin "3") (pinfunction "3_3") (pintype "passive"))
      (node (ref "R16") (pin "2") (pinfunction "2_2") (pintype "passive"))
    )
    (net (code "66") (name "/X7") (class "Default")
      (node (ref "P3") (pin "2") (pinfunction "2_2") (pintype "passive"))
      (node (ref "R26") (pin "2") (pinfunction "2_2") (pintype "passive"))
    )
    (net (code "67") (name "/X8") (class "Default")
      (node (ref "P3") (pin "1") (pinfunction "1_1") (pintype "passive"))
      (node (ref "R32") (pin "2") (pinfunction "2_2") (pintype "passive"))
    )
    (net (code "68") (name "/X9") (class "Default")
      (node (ref "P5") (pin "3") (pinfunction "3_3") (pintype "passive"))
      (node (ref "R5") (pin "2") (pinfunction "2_2") (pintype "passive"))
    )
    (net (code "69") (name "/X10") (class "Default")
      (node (ref "P5") (pin "1") (pinfunction "1_1") (pintype "passive"))
      (node (ref "R17") (pin "2") (pinfunction "2_2") (pintype "passive"))
    )
    (net (code "70") (name "/X11") (class "Default")
      (node (ref "P7") (pin "5") (pinfunction "5_5") (pintype "passive"))
      (node (ref "R27") (pin "2") (pinfunction "2_2") (pintype "passive"))
    )
    (net (code "71") (name "/X12") (class "Default")
      (node (ref "P7") (pin "3") (pinfunction "3_3") (pintype "passive"))
      (node (ref "R33") (pin "2") (pinfunction "2_2") (pintype "passive"))
    )
    (net (code "72") (name "/Y1") (class "Default")
      (node (ref "P2") (pin "1") (pinfunction "1_1") (pintype "passive"))
      (node (ref "U13") (pin "4") (pinfunction "DC+_4") (pintype "passive"))
    )
    (net (code "73") (name "/Y2") (class "Default")
      (node (ref "P2") (pin "3") (pinfunction "3_3") (pintype "passive"))
      (node (ref "U17") (pin "4") (pinfunction "DC+_4") (pintype "passive"))
    )
    (net (code "74") (name "/Y3") (class "Default")
      (node (ref "P4") (pin "1") (pinfunction "1_1") (pintype "passive"))
      (node (ref "U19") (pin "4") (pinfunction "DC+_4") (pintype "passive"))
    )
    (net (code "75") (name "/Y4") (class "Default")
      (node (ref "P4") (pin "3") (pinfunction "3_3") (pintype "passive"))
      (node (ref "U23") (pin "4") (pinfunction "DC+_4") (pintype "passive"))
    )
    (net (code "76") (name "/Y5") (class "Default")
      (node (ref "P6") (pin "1") (pinfunction "1_1") (pintype "passive"))
      (node (ref "U25") (pin "4") (pinfunction "DC+_4") (pintype "passive"))
    )
    (net (code "77") (name "/Y6") (class "Default")
      (node (ref "P6") (pin "3") (pinfunction "3_3") (pintype "passive"))
      (node (ref "U29") (pin "4") (pinfunction "DC+_4") (pintype "passive"))
    )
    (net (code "78") (name "/Y7") (class "Default")
      (node (ref "P8") (pin "1") (pinfunction "1_1") (pintype "passive"))
      (node (ref "U14") (pin "4") (pinfunction "DC+_4") (pintype "passive"))
    )
    (net (code "79") (name "/Y8") (class "Default")
      (node (ref "P8") (pin "3") (pinfunction "3_3") (pintype "passive"))
      (node (ref "U18") (pin "4") (pinfunction "DC+_4") (pintype "passive"))
    )
    (net (code "80") (name "/Y9") (class "Default")
      (node (ref "P8") (pin "4") (pinfunction "4_4") (pintype "passive"))
      (node (ref "U20") (pin "4") (pinfunction "DC+_4") (pintype "passive"))
    )
    (net (code "81") (name "/Y10") (class "Default")
      (node (ref "P9") (pin "1") (pinfunction "1_1") (pintype "passive"))
      (node (ref "U24") (pin "4") (pinfunction "DC+_4") (pintype "passive"))
    )
    (net (code "82") (name "/Y11") (class "Default")
      (node (ref "P9") (pin "2") (pinfunction "2_2") (pintype "passive"))
      (node (ref "U26") (pin "4") (pinfunction "DC+_4") (pintype "passive"))
    )
    (net (code "83") (name "/Y12") (class "Default")
      (node (ref "P9") (pin "3") (pinfunction "3_3") (pintype "passive"))
      (node (ref "U30") (pin "4") (pinfunction "DC+_4") (pintype "passive"))
    )
    (net (code "84") (name "3V3") (class "Default")
      (node (ref "R10") (pin "2") (pinfunction "2_2") (pintype "passive"))
      (node (ref "R18") (pin "2") (pinfunction "2_2") (pintype "passive"))
      (node (ref "R19") (pin "2") (pinfunction "2_2") (pintype "passive"))
      (node (ref "R20") (pin "2") (pinfunction "2_2") (pintype "passive"))
      (node (ref "R28") (pin "2") (pinfunction "2_2") (pintype "passive"))
      (node (ref "R29") (pin "2") (pinfunction "2_2") (pintype "passive"))
      (node (ref "R30") (pin "2") (pinfunction "2_2") (pintype "passive"))
      (node (ref "R34") (pin "2") (pinfunction "2_2") (pintype "passive"))
      (node (ref "R35") (pin "2") (pinfunction "2_2") (pintype "passive"))
      (node (ref "R36") (pin "2") (pinfunction "2_2") (pintype "passive"))
      (node (ref "R8") (pin "2") (pinfunction "2_2") (pintype "passive"))
      (node (ref "R9") (pin "2") (pinfunction "2_2") (pintype "passive"))
    )
    (net (code "85") (name "5V") (class "Default")
      (node (ref "R1") (pin "1") (pinfunction "1_1") (pintype "passive"))
      (node (ref "R11") (pin "1") (pinfunction "1_1") (pintype "passive"))
      (node (ref "R12") (pin "1") (pinfunction "1_1") (pintype "passive"))
      (node (ref "R13") (pin "1") (pinfunction "1_1") (pintype "passive"))
      (node (ref "R14") (pin "1") (pinfunction "1_1") (pintype "passive"))
      (node (ref "R2") (pin "1") (pinfunction "1_1") (pintype "passive"))
      (node (ref "R21") (pin "1") (pinfunction "1_1") (pintype "passive"))
      (node (ref "R22") (pin "1") (pinfunction "1_1") (pintype "passive"))
      (node (ref "R23") (pin "1") (pinfunction "1_1") (pintype "passive"))
      (node (ref "R24") (pin "1") (pinfunction "1_1") (pintype "passive"))
      (node (ref "R37") (pin "2") (pinfunction "2_2") (pintype "passive"))
      (node (ref "R38") (pin "2") (pinfunction "2_2") (pintype "passive"))
      (node (ref "R39") (pin "2") (pinfunction "2_2") (pintype "passive"))
      (node (ref "R40") (pin "2") (pinfunction "2_2") (pintype "passive"))
      (node (ref "R41") (pin "2") (pinfunction "2_2") (pintype "passive"))
      (node (ref "R42") (pin "2") (pinfunction "2_2") (pintype "passive"))
      (node (ref "R43") (pin "2") (pinfunction "2_2") (pintype "passive"))
      (node (ref "R44") (pin "2") (pinfunction "2_2") (pintype "passive"))
      (node (ref "R45") (pin "2") (pinfunction "2_2") (pintype "passive"))
      (node (ref "R46") (pin "2") (pinfunction "2_2") (pintype "passive"))
      (node (ref "R47") (pin "2") (pinfunction "2_2") (pintype "passive"))
      (node (ref "R48") (pin "2") (pinfunction "2_2") (pintype "passive"))
      (node (ref "R6") (pin "1") (pinfunction "1_1") (pintype "passive"))
      (node (ref "R7") (pin "1") (pinfunction "1_1") (pintype "passive"))
    )
    (net (code "86") (name "24V") (class "Default")
      (node (ref "P9") (pin "5") (pinfunction "5_5") (pintype "passive"))
    )
    (net (code "87") (name "GND") (class "Default")
      (node (ref "P9") (pin "4") (pinfunction "4_4") (pintype "passive"))
      (node (ref "P9") (pin "6") (pinfunction "6_6") (pintype "passive"))
      (node (ref "U1") (pin "4") (pinfunction "DC-_4") (pintype "passive"))
      (node (ref "U10") (pin "4") (pinfunction "DC-_4") (pintype "passive"))
      (node (ref "U11") (pin "4") (pinfunction "DC-_4") (pintype "passive"))
      (node (ref "U12") (pin "4") (pinfunction "DC-_4") (pintype "passive"))
      (node (ref "U15") (pin "1") (pinfunction "*_1") (pintype "passive"))
      (node (ref "U15") (pin "4") (pinfunction "*_4") (pintype "passive"))
      (node (ref "U16") (pin "1") (pinfunction "*_1") (pintype "passive"))
      (node (ref "U16") (pin "4") (pinfunction "*_4") (pintype "passive"))
      (node (ref "U2") (pin "4") (pinfunction "DC-_4") (pintype "passive"))
      (node (ref "U21") (pin "1") (pinfunction "*_1") (pintype "passive"))
      (node (ref "U21") (pin "4") (pinfunction "*_4") (pintype "passive"))
      (node (ref "U22") (pin "1") (pinfunction "*_1") (pintype "passive"))
      (node (ref "U22") (pin "4") (pinfunction "*_4") (pintype "passive"))
      (node (ref "U27") (pin "1") (pinfunction "*_1") (pintype "passive"))
      (node (ref "U27") (pin "4") (pinfunction "*_4") (pintype "passive"))
      (node (ref "U28") (pin "1") (pinfunction "*_1") (pintype "passive"))
      (node (ref "U28") (pin "4") (pinfunction "*_4") (pintype "passive"))
      (node (ref "U3") (pin "4") (pinfunction "DC-_4") (pintype "passive"))
      (node (ref "U4") (pin "4") (pinfunction "DC-_4") (pintype "passive"))
      (node (ref "U5") (pin "4") (pinfunction "DC-_4") (pintype "passive"))
      (node (ref "U6") (pin "4") (pinfunction "DC-_4") (pintype "passive"))
      (node (ref "U7") (pin "4") (pinfunction "DC-_4") (pintype "passive"))
      (node (ref "U8") (pin "4") (pinfunction "DC-_4") (pintype "passive"))
      (node (ref "U9") (pin "4") (pinfunction "DC-_4") (pintype "passive"))
    )
    (net (code "88") (name "IN_GND") (class "Default")
      (node (ref "D18") (pin "1") (pinfunction "A_1") (pintype "passive"))
      (node (ref "D19") (pin "1") (pinfunction "A_1") (pintype "passive"))
      (node (ref "D28") (pin "1") (pinfunction "A_1") (pintype "passive"))
      (node (ref "D29") (pin "1") (pinfunction "A_1") (pintype "passive"))
      (node (ref "D31") (pin "2") (pinfunction "K_2") (pintype "passive"))
      (node (ref "D32") (pin "2") (pinfunction "K_2") (pintype "passive"))
      (node (ref "D33") (pin "2") (pinfunction "K_2") (pintype "passive"))
      (node (ref "D34") (pin "2") (pinfunction "K_2") (pintype "passive"))
      (node (ref "D38") (pin "2") (pinfunction "K_2") (pintype "passive"))
      (node (ref "D40") (pin "1") (pinfunction "A_1") (pintype "passive"))
      (node (ref "D41") (pin "1") (pinfunction "A_1") (pintype "passive"))
      (node (ref "D43") (pin "2") (pinfunction "K_2") (pintype "passive"))
      (node (ref "D45") (pin "2") (pinfunction "K_2") (pintype "passive"))
      (node (ref "D47") (pin "2") (pinfunction "K_2") (pintype "passive"))
      (node (ref "D8") (pin "1") (pinfunction "A_1") (pintype "passive"))
      (node (ref "D9") (pin "1") (pinfunction "A_1") (pintype "passive"))
      (node (ref "P5") (pin "4") (pinfunction "4_4") (pintype "passive"))
    )
    (net (code "89") (name "Net-(D1-A)") (class "Default")
      (node (ref "D1") (pin "1") (pinfunction "A_1") (pintype "passive"))
      (node (ref "R1") (pin "2") (pinfunction "2_2") (pintype "passive"))
    )
    (net (code "90") (name "Net-(D2-A)") (class "Default")
      (node (ref "D2") (pin "1") (pinfunction "A_1") (pintype "passive"))
      (node (ref "R2") (pin "2") (pinfunction "2_2") (pintype "passive"))
    )
    (net (code "91") (name "Net-(D3-A)") (class "Default")
      (node (ref "D3") (pin "1") (pinfunction "A_1") (pintype "passive"))
      (node (ref "U1") (pin "1") (pinfunction "control+_1") (pintype "passive"))
    )
    (net (code "92") (name "Net-(D3-K)") (class "Default")
      (node (ref "D3") (pin "2") (pinfunction "K_2") (pintype "passive"))
      (node (ref "D8") (pin "2") (pinfunction "K_2") (pintype "passive"))
      (node (ref "R3") (pin "1") (pinfunction "1_1") (pintype "passive"))
    )
    (net (code "93") (name "Net-(D4-A)") (class "Default")
      (node (ref "D4") (pin "1") (pinfunction "A_1") (pintype "passive"))
      (node (ref "U2") (pin "1") (pinfunction "control+_1") (pintype "passive"))
    )
    (net (code "94") (name "Net-(D4-K)") (class "Default")
      (node (ref "D4") (pin "2") (pinfunction "K_2") (pintype "passive"))
      (node (ref "D9") (pin "2") (pinfunction "K_2") (pintype "passive"))
      (node (ref "R4") (pin "1") (pinfunction "1_1") (pintype "passive"))
    )
    (net (code "95") (name "Net-(D5-A)") (class "Default")
      (node (ref "D5") (pin "1") (pinfunction "A_1") (pintype "passive"))
      (node (ref "U3") (pin "1") (pinfunction "control+_1") (pintype "passive"))
    )
    (net (code "96") (name "Net-(D6-A)") (class "Default")
      (node (ref "D6") (pin "1") (pinfunction "A_1") (pintype "passive"))
      (node (ref "R6") (pin "2") (pinfunction "2_2") (pintype "passive"))
    )
    (net (code "97") (name "Net-(D7-A)") (class "Default")
      (node (ref "D7") (pin "1") (pinfunction "A_1") (pintype "passive"))
      (node (ref "R7") (pin "2") (pinfunction "2_2") (pintype "passive"))
    )
    (net (code "98") (name "Net-(D10-K)") (class "Default")
      (node (ref "D10") (pin "2") (pinfunction "K_2") (pintype "passive"))
      (node (ref "D5") (pin "2") (pinfunction "K_2") (pintype "passive"))
      (node (ref "R5") (pin "1") (pinfunction "1_1") (pintype "passive"))
    )
    (net (code "99") (name "Net-(D11-A)") (class "Default")
      (node (ref "D11") (pin "1") (pinfunction "A_1") (pintype "passive"))
      (node (ref "R11") (pin "2") (pinfunction "2_2") (pintype "passive"))
    )
    (net (code "100") (name "Net-(D12-A)") (class "Default")
      (node (ref "D12") (pin "1") (pinfunction "A_1") (pintype "passive"))
      (node (ref "R12") (pin "2") (pinfunction "2_2") (pintype "passive"))
    )
    (net (code "101") (name "Net-(D13-A)") (class "Default")
      (node (ref "D13") (pin "1") (pinfunction "A_1") (pintype "passive"))
      (node (ref "R13") (pin "2") (pinfunction "2_2") (pintype "passive"))
    )
    (net (code "102") (name "Net-(D14-A)") (class "Default")
      (node (ref "D14") (pin "1") (pinfunction "A_1") (pintype "passive"))
      (node (ref "R14") (pin "2") (pinfunction "2_2") (pintype "passive"))
    )
    (net (code "103") (name "Net-(D15-A)") (class "Default")
      (node (ref "D15") (pin "1") (pinfunction "A_1") (pintype "passive"))
      (node (ref "U4") (pin "1") (pinfunction "control+_1") (pintype "passive"))
    )
    (net (code "104") (name "Net-(D15-K)") (class "Default")
      (node (ref "D15") (pin "2") (pinfunction "K_2") (pintype "passive"))
      (node (ref "D18") (pin "2") (pinfunction "K_2") (pintype "passive"))
      (node (ref "R15") (pin "1") (pinfunction "1_1") (pintype "passive"))
    )
    (net (code "105") (name "Net-(D16-A)") (class "Default")
      (node (ref "D16") (pin "1") (pinfunction "A_1") (pintype "passive"))
      (node (ref "U5") (pin "1") (pinfunction "control+_1") (pintype "passive"))
    )
    (net (code "106") (name "Net-(D16-K)") (class "Default")
      (node (ref "D16") (pin "2") (pinfunction "K_2") (pintype "passive"))
      (node (ref "D19") (pin "2") (pinfunction "K_2") (pintype "passive"))
      (node (ref "R16") (pin "1") (pinfunction "1_1") (pintype "passive"))
    )
    (net (code "107") (name "Net-(D17-A)") (class "Default")
      (node (ref "D17") (pin "1") (pinfunction "A_1") (pintype "passive"))
      (node (ref "U6") (pin "1") (pinfunction "control+_1") (pintype "passive"))
    )
    (net (code "108") (name "Net-(D17-K)") (class "Default")
      (node (ref "D17") (pin "2") (pinfunction "K_2") (pintype "passive"))
      (node (ref "D20") (pin "2") (pinfunction "K_2") (pintype "passive"))
      (node (ref "R17") (pin "1") (pinfunction "1_1") (pintype "passive"))
    )
    (net (code "109") (name "Net-(D21-A)") (class "Default")
      (node (ref "D21") (pin "1") (pinfunction "A_1") (pintype "passive"))
      (node (ref "R21") (pin "2") (pinfunction "2_2") (pintype "passive"))
    )
    (net (code "110") (name "Net-(D22-A)") (class "Default")
      (node (ref "D22") (pin "1") (pinfunction "A_1") (pintype "passive"))
      (node (ref "R22") (pin "2") (pinfunction "2_2") (pintype "passive"))
    )
    (net (code "111") (name "Net-(D23-A)") (class "Default")
      (node (ref "D23") (pin "1") (pinfunction "A_1") (pintype "passive"))
      (node (ref "R23") (pin "2") (pinfunction "2_2") (pintype "passive"))
    )
    (net (code "112") (name "Net-(D24-A)") (class "Default")
      (node (ref "D24") (pin "1") (pinfunction "A_1") (pintype "passive"))
      (node (ref "R24") (pin "2") (pinfunction "2_2") (pintype "passive"))
    )
    (net (code "113") (name "Net-(D25-A)") (class "Default")
      (node (ref "D25") (pin "1") (pinfunction "A_1") (pintype "passive"))
      (node (ref "U7") (pin "1") (pinfunction "control+_1") (pintype "passive"))
    )
    (net (code "114") (name "Net-(D25-K)") (class "Default")
      (node (ref "D25") (pin "2") (pinfunction "K_2") (pintype "passive"))
      (node (ref "D28") (pin "2") (pinfunction "K_2") (pintype "passive"))
      (node (ref "R25") (pin "1") (pinfunction "1_1") (pintype "passive"))
    )
    (net (code "115") (name "Net-(D26-A)") (class "Default")
      (node (ref "D26") (pin "1") (pinfunction "A_1") (pintype "passive"))
      (node (ref "U8") (pin "1") (pinfunction "control+_1") (pintype "passive"))
    )
    (net (code "116") (name "Net-(D26-K)") (class "Default")
      (node (ref "D26") (pin "2") (pinfunction "K_2") (pintype "passive"))
      (node (ref "D29") (pin "2") (pinfunction "K_2") (pintype "passive"))
      (node (ref "R26") (pin "1") (pinfunction "1_1") (pintype "passive"))
    )
    (net (code "117") (name "Net-(D27-A)") (class "Default")
      (node (ref "D27") (pin "1") (pinfunction "A_1") (pintype "passive"))
      (node (ref "U9") (pin "1") (pinfunction "control+_1") (pintype "passive"))
    )
    (net (code "118") (name "Net-(D27-K)") (class "Default")
      (node (ref "D27") (pin "2") (pinfunction "K_2") (pintype "passive"))
      (node (ref "D30") (pin "2") (pinfunction "K_2") (pintype "passive"))
      (node (ref "R27") (pin "1") (pinfunction "1_1") (pintype "passive"))
    )
    (net (code "119") (name "Net-(D35-A)") (class "Default")
      (node (ref "D35") (pin "1") (pinfunction "A_1") (pintype "passive"))
      (node (ref "U10") (pin "1") (pinfunction "control+_1") (pintype "passive"))
    )
    (net (code "120") (name "Net-(D35-K)") (class "Default")
      (node (ref "D35") (pin "2") (pinfunction "K_2") (pintype "passive"))
      (node (ref "D40") (pin "2") (pinfunction "K_2") (pintype "passive"))
      (node (ref "R31") (pin "1") (pinfunction "1_1") (pintype "passive"))
    )
    (net (code "121") (name "Net-(D36-A)") (class "Default")
      (node (ref "D36") (pin "1") (pinfunction "A_1") (pintype "passive"))
      (node (ref "U11") (pin "1") (pinfunction "control+_1") (pintype "passive"))
    )
    (net (code "122") (name "Net-(D36-K)") (class "Default")
      (node (ref "D36") (pin "2") (pinfunction "K_2") (pintype "passive"))
      (node (ref "D41") (pin "2") (pinfunction "K_2") (pintype "passive"))
      (node (ref "R32") (pin "1") (pinfunction "1_1") (pintype "passive"))
    )
    (net (code "123") (name "Net-(D37-A)") (class "Default")
      (node (ref "D37") (pin "1") (pinfunction "A_1") (pintype "passive"))
      (node (ref "U12") (pin "1") (pinfunction "control+_1") (pintype "passive"))
    )
    (net (code "124") (name "Net-(D37-K)") (class "Default")
      (node (ref "D37") (pin "2") (pinfunction "K_2") (pintype "passive"))
      (node (ref "D42") (pin "2") (pinfunction "K_2") (pintype "passive"))
      (node (ref "R33") (pin "1") (pinfunction "1_1") (pintype "passive"))
    )
    (net (code "125") (name "Net-(U13-control+)") (class "Default")
      (node (ref "R37") (pin "1") (pinfunction "1_1") (pintype "passive"))
      (node (ref "U13") (pin "1") (pinfunction "control+_1") (pintype "passive"))
    )
    (net (code "126") (name "Net-(U14-control+)") (class "Default")
      (node (ref "R38") (pin "1") (pinfunction "1_1") (pintype "passive"))
      (node (ref "U14") (pin "1") (pinfunction "control+_1") (pintype "passive"))
    )
    (net (code "127") (name "Net-(U17-control+)") (class "Default")
      (node (ref "R39") (pin "1") (pinfunction "1_1") (pintype "passive"))
      (node (ref "U17") (pin "1") (pinfunction "control+_1") (pintype "passive"))
    )
    (net (code "128") (name "Net-(U18-control+)") (class "Default")
      (node (ref "R40") (pin "1") (pinfunction "1_1") (pintype "passive"))
      (node (ref "U18") (pin "1") (pinfunction "control+_1") (pintype "passive"))
    )
    (net (code "129") (name "Net-(U19-control+)") (class "Default")
      (node (ref "R41") (pin "1") (pinfunction "1_1") (pintype "passive"))
      (node (ref "U19") (pin "1") (pinfunction "control+_1") (pintype "passive"))
    )
    (net (code "130") (name "Net-(U20-control+)") (class "Default")
      (node (ref "R42") (pin "1") (pinfunction "1_1") (pintype "passive"))
      (node (ref "U20") (pin "1") (pinfunction "control+_1") (pintype "passive"))
    )
    (net (code "131") (name "Net-(U23-control+)") (class "Default")
      (node (ref "R43") (pin "1") (pinfunction "1_1") (pintype "passive"))
      (node (ref "U23") (pin "1") (pinfunction "control+_1") (pintype "passive"))
    )
    (net (code "132") (name "Net-(U24-control+)") (class "Default")
      (node (ref "R44") (pin "1") (pinfunction "1_1") (pintype "passive"))
      (node (ref "U24") (pin "1") (pinfunction "control+_1") (pintype "passive"))
    )
    (net (code "133") (name "Net-(U25-control+)") (class "Default")
      (node (ref "R45") (pin "1") (pinfunction "1_1") (pintype "passive"))
      (node (ref "U25") (pin "1") (pinfunction "control+_1") (pintype "passive"))
    )
    (net (code "134") (name "Net-(U26-control+)") (class "Default")
      (node (ref "R46") (pin "1") (pinfunction "1_1") (pintype "passive"))
      (node (ref "U26") (pin "1") (pinfunction "control+_1") (pintype "passive"))
    )
    (net (code "135") (name "Net-(U29-control+)") (class "Default")
      (node (ref "R47") (pin "1") (pinfunction "1_1") (pintype "passive"))
      (node (ref "U29") (pin "1") (pinfunction "control+_1") (pintype "passive"))
    )
    (net (code "136") (name "Net-(U30-control+)") (class "Default")
      (node (ref "R48") (pin "1") (pinfunction "1_1") (pintype "passive"))
      (node (ref "U30") (pin "1") (pinfunction "control+_1") (pintype "passive"))
    )
    (net (code "137") (name "unconnected-(P7-Pad1)") (class "Default")
      (node (ref "P7") (pin "1") (pinfunction "1_1") (pintype "passive+no_connect"))
    )
  )
)
